# main-board-SCHEMATIC.net
KiCad netlist of a schematic drawn in Altium Designer
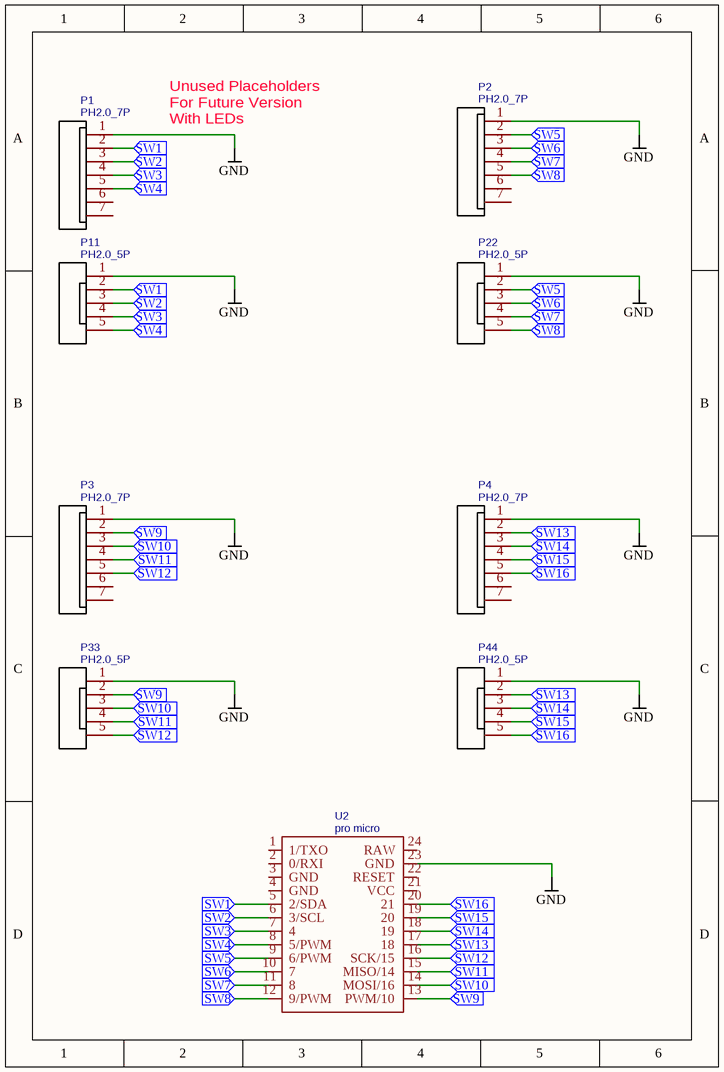
[diagram p0: main-board-SCHEMATIC.schdoc]

(export (version "E")
  (design (tool "Eeschema 10.0.6"))
  (components
    (comp (ref "P1")
      (value "PH2.0_7P")
      (fields (field (name "MANUFACTURER PART") "New SchematicLib") (field (name "CONTRIBUTOR") "robellado"))
      (libsource (lib "altium-import") (part "root_0_PH2.0_7P_"))
    )
    (comp (ref "P2")
      (value "PH2.0_7P")
      (fields (field (name "MANUFACTURER PART") "New SchematicLib") (field (name "CONTRIBUTOR") "robellado"))
      (libsource (lib "altium-import") (part "root_0_PH2.0_7P_"))
    )
    (comp (ref "P3")
      (value "PH2.0_7P")
      (fields (field (name "MANUFACTURER PART") "New SchematicLib") (field (name "CONTRIBUTOR") "robellado"))
      (libsource (lib "altium-import") (part "root_0_PH2.0_7P_"))
    )
    (comp (ref "P4")
      (value "PH2.0_7P")
      (fields (field (name "MANUFACTURER PART") "New SchematicLib") (field (name "CONTRIBUTOR") "robellado"))
      (libsource (lib "altium-import") (part "root_0_PH2.0_7P_"))
    )
    (comp (ref "P11")
      (value "PH2.0_5P")
      (fields
        (field (name "MANUFACTURER PART") "New SchematicLib")
        (field (name "CONTRIBUTOR") "oleg.evsegneev")
      )
      (libsource (lib "altium-import") (part "root_0_PH2.0_5P_"))
    )
    (comp (ref "P22")
      (value "PH2.0_5P")
      (fields
        (field (name "MANUFACTURER PART") "New SchematicLib")
        (field (name "CONTRIBUTOR") "oleg.evsegneev")
      )
      (libsource (lib "altium-import") (part "root_0_PH2.0_5P_"))
    )
    (comp (ref "P33")
      (value "PH2.0_5P")
      (fields
        (field (name "MANUFACTURER PART") "New SchematicLib")
        (field (name "CONTRIBUTOR") "oleg.evsegneev")
      )
      (libsource (lib "altium-import") (part "root_0_PH2.0_5P_"))
    )
    (comp (ref "P44")
      (value "PH2.0_5P")
      (fields
        (field (name "MANUFACTURER PART") "New SchematicLib")
        (field (name "CONTRIBUTOR") "oleg.evsegneev")
      )
      (libsource (lib "altium-import") (part "root_0_PH2.0_5P_"))
    )
    (comp (ref "U2")
      (value "pro micro")
      (fields (field (name "CONTRIBUTOR") "Chris Cullin"))
      (libsource (lib "altium-import") (part "root_0_pro micro_"))
    )
  )
  (nets
    (net (code "1") (name "/SW1") (class "Default")
      (node (ref "P1") (pin "2") (pinfunction "2_2") (pintype "passive"))
      (node (ref "P11") (pin "2") (pinfunction "2_2") (pintype "passive"))
      (node (ref "U2") (pin "5") (pinfunction "2/SDA_5") (pintype "passive"))
    )
    (net (code "2") (name "/SW2") (class "Default")
      (node (ref "P1") (pin "3") (pinfunction "3_3") (pintype "passive"))
      (node (ref "P11") (pin "3") (pinfunction "3_3") (pintype "passive"))
      (node (ref "U2") (pin "6") (pinfunction "3/SCL_6") (pintype "passive"))
    )
    (net (code "3") (name "/SW3") (class "Default")
      (node (ref "P1") (pin "4") (pinfunction "4_4") (pintype "passive"))
      (node (ref "P11") (pin "4") (pinfunction "4_4") (pintype "passive"))
      (node (ref "U2") (pin "7") (pinfunction "4_7") (pintype "passive"))
    )
    (net (code "4") (name "/SW4") (class "Default")
      (node (ref "P1") (pin "5") (pinfunction "5_5") (pintype "passive"))
      (node (ref "P11") (pin "5") (pinfunction "5_5") (pintype "passive"))
      (node (ref "U2") (pin "8") (pinfunction "5/PWM_8") (pintype "passive"))
    )
    (net (code "5") (name "/SW5") (class "Default")
      (node (ref "P2") (pin "2") (pinfunction "2_2") (pintype "passive"))
      (node (ref "P22") (pin "2") (pinfunction "2_2") (pintype "passive"))
      (node (ref "U2") (pin "9") (pinfunction "6/PWM_9") (pintype "passive"))
    )
    (net (code "6") (name "/SW6") (class "Default")
      (node (ref "P2") (pin "3") (pinfunction "3_3") (pintype "passive"))
      (node (ref "P22") (pin "3") (pinfunction "3_3") (pintype "passive"))
      (node (ref "U2") (pin "10") (pinfunction "7_10") (pintype "passive"))
    )
    (net (code "7") (name "/SW7") (class "Default")
      (node (ref "P2") (pin "4") (pinfunction "4_4") (pintype "passive"))
      (node (ref "P22") (pin "4") (pinfunction "4_4") (pintype "passive"))
      (node (ref "U2") (pin "11") (pinfunction "8_11") (pintype "passive"))
    )
    (net (code "8") (name "/SW8") (class "Default")
      (node (ref "P2") (pin "5") (pinfunction "5_5") (pintype "passive"))
      (node (ref "P22") (pin "5") (pinfunction "5_5") (pintype "passive"))
      (node (ref "U2") (pin "12") (pinfunction "9/PWM_12") (pintype "passive"))
    )
    (net (code "9") (name "/SW9") (class "Default")
      (node (ref "P3") (pin "2") (pinfunction "2_2") (pintype "passive"))
      (node (ref "P33") (pin "2") (pinfunction "2_2") (pintype "passive"))
      (node (ref "U2") (pin "13") (pinfunction "PWM/10_13") (pintype "passive"))
    )
    (net (code "10") (name "/SW10") (class "Default")
      (node (ref "P3") (pin "3") (pinfunction "3_3") (pintype "passive"))
      (node (ref "P33") (pin "3") (pinfunction "3_3") (pintype "passive"))
      (node (ref "U2") (pin "14") (pinfunction "MOSI/16_14") (pintype "passive"))
    )
    (net (code "11") (name "/SW11") (class "Default")
      (node (ref "P3") (pin "4") (pinfunction "4_4") (pintype "passive"))
      (node (ref "P33") (pin "4") (pinfunction "4_4") (pintype "passive"))
      (node (ref "U2") (pin "15") (pinfunction "MISO/14_15") (pintype "passive"))
    )
    (net (code "12") (name "/SW12") (class "Default")
      (node (ref "P3") (pin "5") (pinfunction "5_5") (pintype "passive"))
      (node (ref "P33") (pin "5") (pinfunction "5_5") (pintype "passive"))
      (node (ref "U2") (pin "16") (pinfunction "SCK/15_16") (pintype "passive"))
    )
    (net (code "13") (name "/SW13") (class "Default")
      (node (ref "P4") (pin "2") (pinfunction "2_2") (pintype "passive"))
      (node (ref "P44") (pin "2") (pinfunction "2_2") (pintype "passive"))
      (node (ref "U2") (pin "17") (pinfunction "18_17") (pintype "passive"))
    )
    (net (code "14") (name "/SW14") (class "Default")
      (node (ref "P4") (pin "3") (pinfunction "3_3") (pintype "passive"))
      (node (ref "P44") (pin "3") (pinfunction "3_3") (pintype "passive"))
      (node (ref "U2") (pin "18") (pinfunction "19_18") (pintype "passive"))
    )
    (net (code "15") (name "/SW15") (class "Default")
      (node (ref "P4") (pin "4") (pinfunction "4_4") (pintype "passive"))
      (node (ref "P44") (pin "4") (pinfunction "4_4") (pintype "passive"))
      (node (ref "U2") (pin "19") (pinfunction "20_19") (pintype "passive"))
    )
    (net (code "16") (name "/SW16") (class "Default")
      (node (ref "P4") (pin "5") (pinfunction "5_5") (pintype "passive"))
      (node (ref "P44") (pin "5") (pinfunction "5_5") (pintype "passive"))
      (node (ref "U2") (pin "20") (pinfunction "21_20") (pintype "passive"))
    )
    (net (code "17") (name "GND") (class "Default")
      (node (ref "P1") (pin "1") (pinfunction "1_1") (pintype "passive"))
      (node (ref "P11") (pin "1") (pinfunction "1_1") (pintype "passive"))
      (node (ref "P2") (pin "1") (pinfunction "1_1") (pintype "passive"))
      (node (ref "P22") (pin "1") (pinfunction "1_1") (pintype "passive"))
      (node (ref "P3") (pin "1") (pinfunction "1_1") (pintype "passive"))
      (node (ref "P33") (pin "1") (pinfunction "1_1") (pintype "passive"))
      (node (ref "P4") (pin "1") (pinfunction "1_1") (pintype "passive"))
      (node (ref "P44") (pin "1") (pinfunction "1_1") (pintype "passive"))
      (node (ref "U2") (pin "23") (pinfunction "GND_23") (pintype "passive"))
    )
    (net (code "18") (name "unconnected-(P1-Pad6)") (class "Default")
      (node (ref "P1") (pin "6") (pinfunction "6_6") (pintype "passive"))
    )
    (net (code "19") (name "unconnected-(P1-Pad7)") (class "Default")
      (node (ref "P1") (pin "7") (pinfunction "7_7") (pintype "passive"))
    )
    (net (code "20") (name "unconnected-(P2-Pad6)") (class "Default")
      (node (ref "P2") (pin "6") (pinfunction "6_6") (pintype "passive"))
    )
    (net (code "21") (name "unconnected-(P2-Pad7)") (class "Default")
      (node (ref "P2") (pin "7") (pinfunction "7_7") (pintype "passive"))
    )
    (net (code "22") (name "unconnected-(P3-Pad6)") (class "Default")
      (node (ref "P3") (pin "6") (pinfunction "6_6") (pintype "passive"))
    )
    (net (code "23") (name "unconnected-(P3-Pad7)") (class "Default")
      (node (ref "P3") (pin "7") (pinfunction "7_7") (pintype "passive"))
    )
    (net (code "24") (name "unconnected-(P4-Pad6)") (class "Default")
      (node (ref "P4") (pin "6") (pinfunction "6_6") (pintype "passive"))
    )
    (net (code "25") (name "unconnected-(P4-Pad7)") (class "Default")
      (node (ref "P4") (pin "7") (pinfunction "7_7") (pintype "passive"))
    )
    (net (code "26") (name "unconnected-(U2-0{slash}RXI-Pad2)") (class "Default")
      (node (ref "U2") (pin "2") (pinfunction "0/RXI_2") (pintype "passive"))
    )
    (net (code "27") (name "unconnected-(U2-1{slash}TXO-Pad1)") (class "Default")
      (node (ref "U2") (pin "1") (pinfunction "1/TXO_1") (pintype "passive"))
    )
    (net (code "28") (name "unconnected-(U2-GND-Pad3)") (class "Default")
      (node (ref "U2") (pin "3") (pinfunction "GND_3") (pintype "passive"))
    )
    (net (code "29") (name "unconnected-(U2-GND-Pad4)") (class "Default")
      (node (ref "U2") (pin "4") (pinfunction "GND_4") (pintype "passive"))
    )
    (net (code "30") (name "unconnected-(U2-RAW-Pad24)") (class "Default")
      (node (ref "U2") (pin "24") (pinfunction "RAW_24") (pintype "passive"))
    )
    (net (code "31") (name "unconnected-(U2-RESET-Pad22)") (class "Default")
      (node (ref "U2") (pin "22") (pinfunction "RESET_22") (pintype "passive"))
    )
    (net (code "32") (name "unconnected-(U2-VCC-Pad21)") (class "Default")
      (node (ref "U2") (pin "21") (pinfunction "VCC_21") (pintype "passive"))
    )
  )
)
